# 0x6Connection.net
KiCad netlist of a schematic drawn in EAGLE
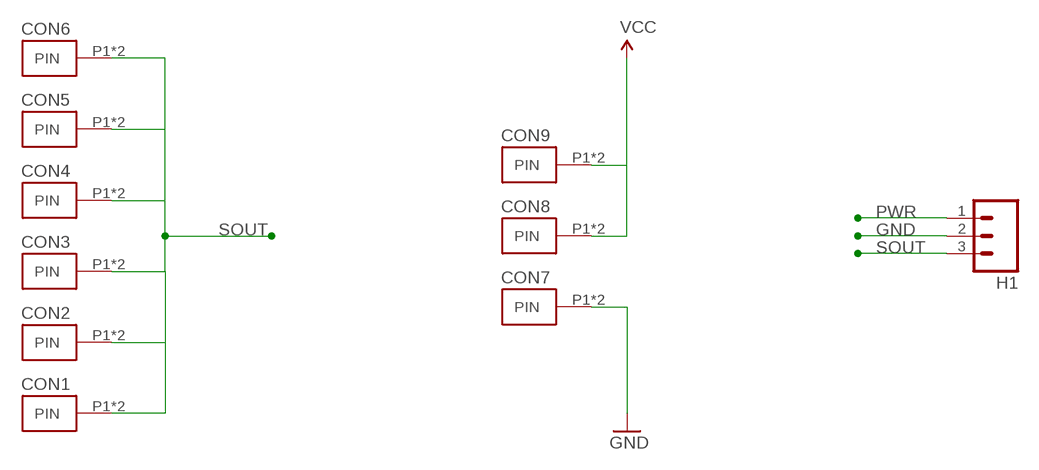
[diagram p0: schematic, sheet 1]

(export (version "E")
  (design (tool "Eeschema 10.0.6"))
  (components
    (comp (ref "CON1")
      (value "SHIELD_FINGER0820")
      (footprint "eagle-import:SHIELD_FINGER_PKG")
      (libsource (lib "eagle-import") (part "SHIELD_FINGER0820"))
    )
    (comp (ref "CON2")
      (value "SHIELD_FINGER0820")
      (footprint "eagle-import:SHIELD_FINGER_PKG")
      (libsource (lib "eagle-import") (part "SHIELD_FINGER0820"))
    )
    (comp (ref "CON3")
      (value "SHIELD_FINGER0820")
      (footprint "eagle-import:SHIELD_FINGER_PKG")
      (libsource (lib "eagle-import") (part "SHIELD_FINGER0820"))
    )
    (comp (ref "CON4")
      (value "SHIELD_FINGER0820")
      (footprint "eagle-import:SHIELD_FINGER_PKG")
      (libsource (lib "eagle-import") (part "SHIELD_FINGER0820"))
    )
    (comp (ref "CON5")
      (value "SHIELD_FINGER0820")
      (footprint "eagle-import:SHIELD_FINGER_PKG")
      (libsource (lib "eagle-import") (part "SHIELD_FINGER0820"))
    )
    (comp (ref "CON6")
      (value "SHIELD_FINGER0820")
      (footprint "eagle-import:SHIELD_FINGER_PKG")
      (libsource (lib "eagle-import") (part "SHIELD_FINGER0820"))
    )
    (comp (ref "CON7")
      (value "SHIELD_FINGER0820")
      (footprint "eagle-import:SHIELD_FINGER_PKG")
      (libsource (lib "eagle-import") (part "SHIELD_FINGER0820"))
    )
    (comp (ref "CON8")
      (value "SHIELD_FINGER0820")
      (footprint "eagle-import:SHIELD_FINGER_PKG")
      (libsource (lib "eagle-import") (part "SHIELD_FINGER0820"))
    )
    (comp (ref "CON9")
      (value "SHIELD_FINGER0820")
      (footprint "eagle-import:SHIELD_FINGER_PKG")
      (libsource (lib "eagle-import") (part "SHIELD_FINGER0820"))
    )
    (comp (ref "H1")
      (value "M031X03_NO_HOLES")
      (footprint "eagle-import:1X03_NO_HOLES")
      (libsource (lib "eagle-import") (part "M031X03_NO_HOLES"))
    )
  )
  (nets
    (net (code "1") (name "/SOUT") (class "Default")
      (node (ref "CON1") (pin "P1") (pinfunction "PIN_P1") (pintype "bidirectional"))
      (node (ref "CON1") (pin "P2") (pinfunction "PIN_P2") (pintype "bidirectional"))
      (node (ref "CON2") (pin "P1") (pinfunction "PIN_P1") (pintype "bidirectional"))
      (node (ref "CON2") (pin "P2") (pinfunction "PIN_P2") (pintype "bidirectional"))
      (node (ref "CON3") (pin "P1") (pinfunction "PIN_P1") (pintype "bidirectional"))
      (node (ref "CON3") (pin "P2") (pinfunction "PIN_P2") (pintype "bidirectional"))
      (node (ref "CON4") (pin "P1") (pinfunction "PIN_P1") (pintype "bidirectional"))
      (node (ref "CON4") (pin "P2") (pinfunction "PIN_P2") (pintype "bidirectional"))
      (node (ref "CON5") (pin "P1") (pinfunction "PIN_P1") (pintype "bidirectional"))
      (node (ref "CON5") (pin "P2") (pinfunction "PIN_P2") (pintype "bidirectional"))
      (node (ref "CON6") (pin "P1") (pinfunction "PIN_P1") (pintype "bidirectional"))
      (node (ref "CON6") (pin "P2") (pinfunction "PIN_P2") (pintype "bidirectional"))
      (node (ref "H1") (pin "3") (pinfunction "3_3") (pintype "passive"))
    )
    (net (code "2") (name "GND") (class "Default")
      (node (ref "CON7") (pin "P1") (pinfunction "PIN_P1") (pintype "bidirectional"))
      (node (ref "CON7") (pin "P2") (pinfunction "PIN_P2") (pintype "bidirectional"))
      (node (ref "H1") (pin "2") (pinfunction "2_2") (pintype "passive"))
    )
    (net (code "3") (name "VCC") (class "Default")
      (node (ref "CON8") (pin "P1") (pinfunction "PIN_P1") (pintype "bidirectional"))
      (node (ref "CON8") (pin "P2") (pinfunction "PIN_P2") (pintype "bidirectional"))
      (node (ref "CON9") (pin "P1") (pinfunction "PIN_P1") (pintype "bidirectional"))
      (node (ref "CON9") (pin "P2") (pinfunction "PIN_P2") (pintype "bidirectional"))
      (node (ref "H1") (pin "1") (pinfunction "1_1") (pintype "passive"))
    )
  )
)
